# master_jorge.net
KiCad netlist of a schematic drawn in EAGLE
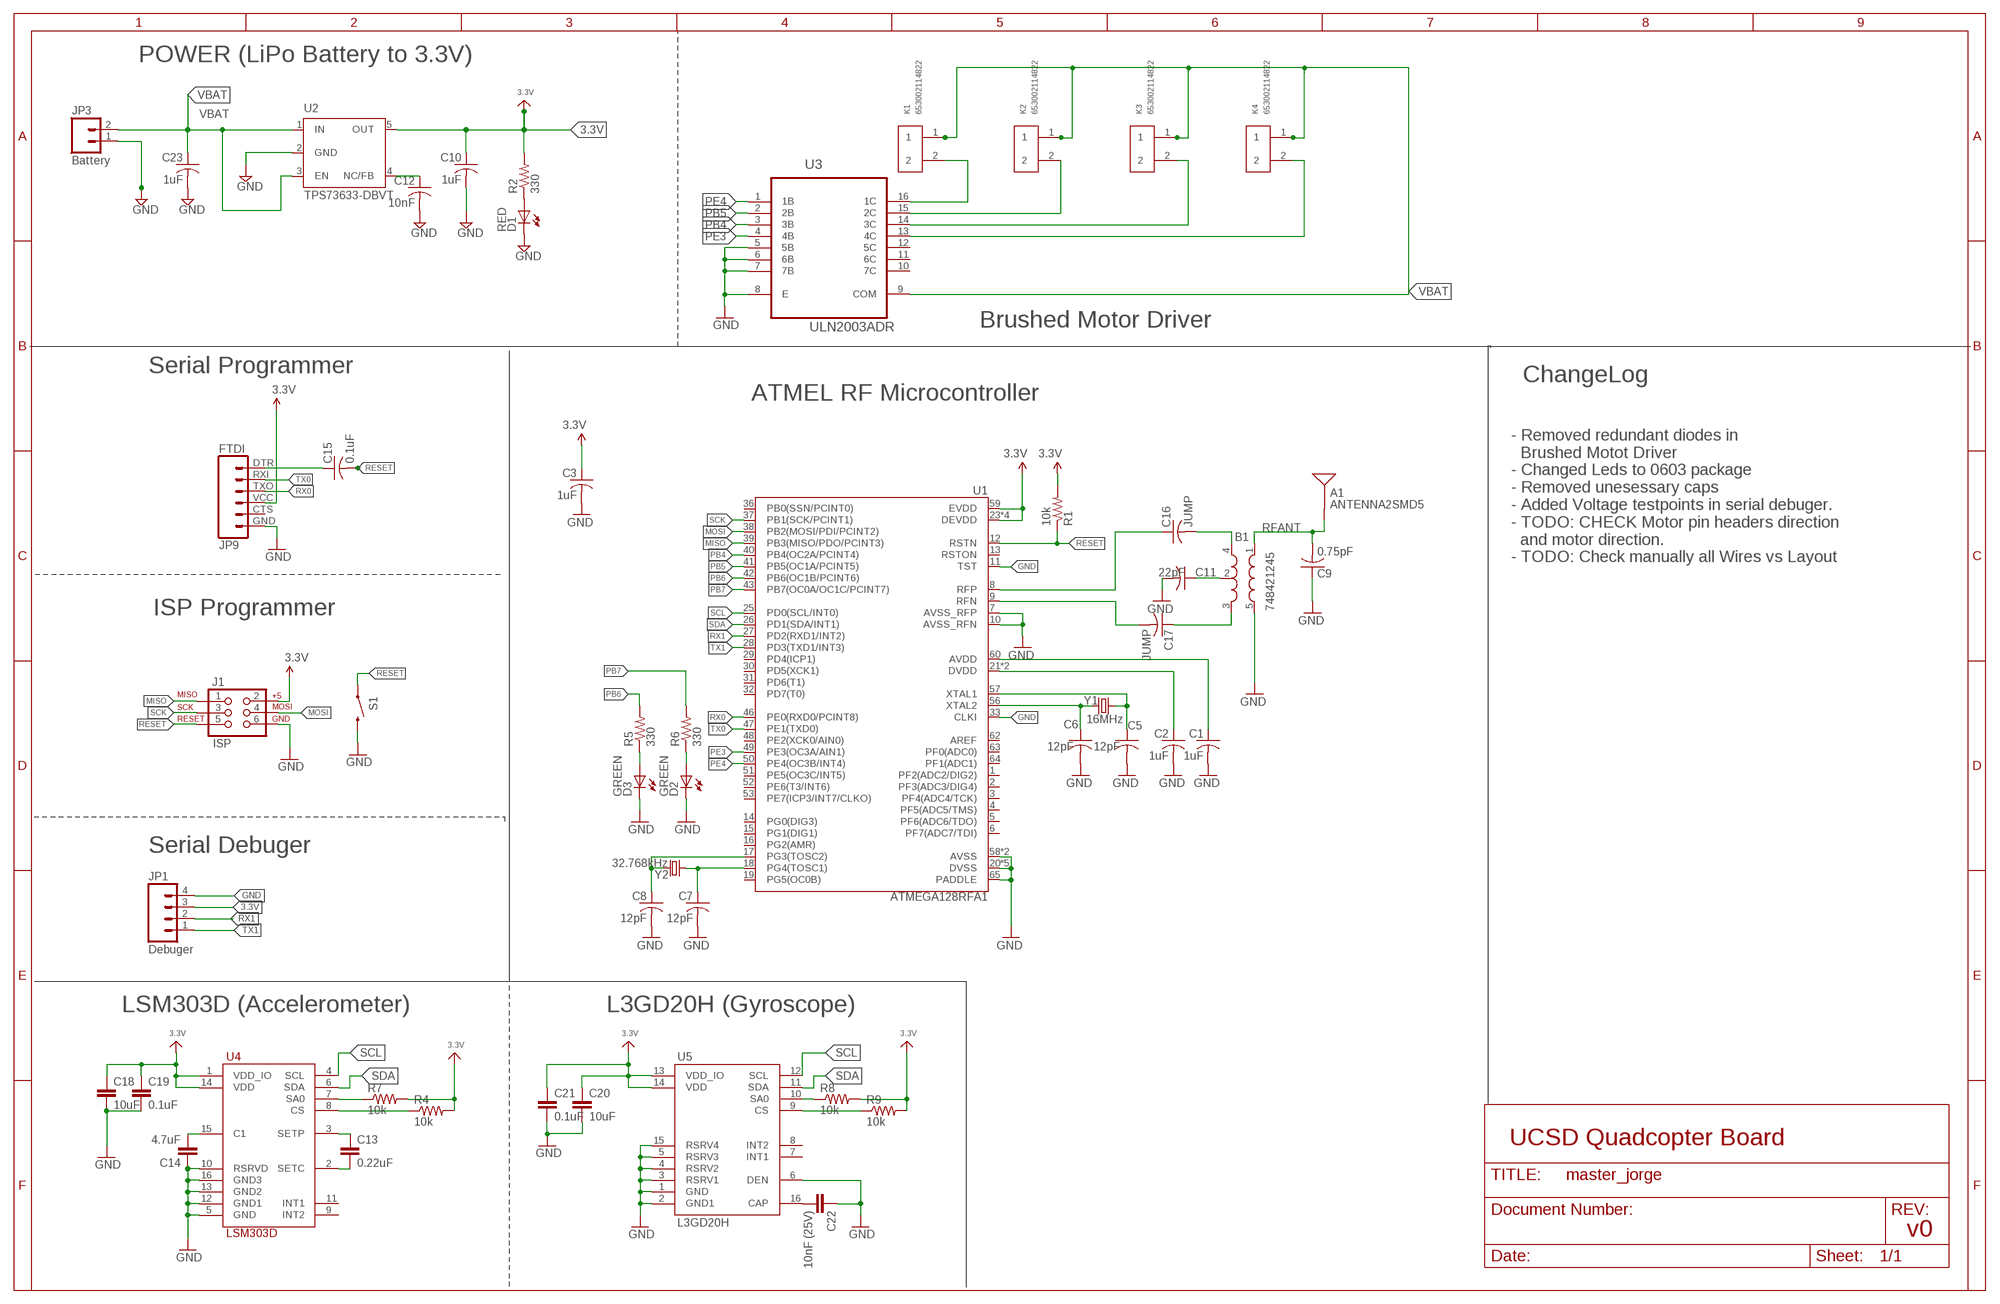
[diagram p0: schematic, sheet 1]

(export (version "E")
  (design (tool "Eeschema 10.0.6"))
  (components
    (comp (ref "A1")
      (value "ANTENNA2SMD5")
      (footprint "eagle-import:ANTENNA-CHIP5")
      (libsource (lib "eagle-import") (part "ANTENNA2SMD5"))
    )
    (comp (ref "B1")
      (value "748421245")
      (footprint "eagle-import:BALUN")
      (libsource (lib "eagle-import") (part "BALUN0805"))
    )
    (comp (ref "C1")
      (value "1uF")
      (footprint "eagle-import:C0805")
      (libsource (lib "eagle-import") (part "C-USC0805"))
    )
    (comp (ref "C2")
      (value "1uF")
      (footprint "eagle-import:C0805")
      (libsource (lib "eagle-import") (part "C-USC0805"))
    )
    (comp (ref "C3")
      (value "1uF")
      (footprint "eagle-import:C0805")
      (libsource (lib "eagle-import") (part "C-USC0805"))
    )
    (comp (ref "C5")
      (value "12pF")
      (footprint "eagle-import:C0805")
      (libsource (lib "eagle-import") (part "C-USC0805"))
    )
    (comp (ref "C6")
      (value "12pF")
      (footprint "eagle-import:C0805")
      (libsource (lib "eagle-import") (part "C-USC0805"))
    )
    (comp (ref "C7")
      (value "12pF")
      (footprint "eagle-import:C0805")
      (libsource (lib "eagle-import") (part "C-USC0805"))
    )
    (comp (ref "C8")
      (value "12pF")
      (footprint "eagle-import:C0805")
      (libsource (lib "eagle-import") (part "C-USC0805"))
    )
    (comp (ref "C9")
      (value "0.75pF")
      (footprint "eagle-import:C0805")
      (libsource (lib "eagle-import") (part "C-USC0805"))
    )
    (comp (ref "C10")
      (value "1uF")
      (footprint "eagle-import:C0805")
      (libsource (lib "eagle-import") (part "C-USC0805"))
    )
    (comp (ref "C11")
      (value "22pF")
      (footprint "eagle-import:C0805")
      (libsource (lib "eagle-import") (part "C-USC0805"))
    )
    (comp (ref "C12")
      (value "10nF")
      (footprint "eagle-import:C0805")
      (libsource (lib "eagle-import") (part "C-USC0805"))
    )
    (comp (ref "C13")
      (value "0.22uF")
      (footprint "eagle-import:0805")
      (libsource (lib "eagle-import") (part "CAP0805"))
    )
    (comp (ref "C14")
      (value "4.7uF")
      (footprint "eagle-import:0805")
      (libsource (lib "eagle-import") (part "CAP0805"))
    )
    (comp (ref "C15")
      (value "0.1uF")
      (footprint "eagle-import:C0805")
      (libsource (lib "eagle-import") (part "C-USC0805"))
    )
    (comp (ref "C16")
      (value "JUMP")
      (footprint "eagle-import:C0805")
      (libsource (lib "eagle-import") (part "C-USC0805"))
    )
    (comp (ref "C17")
      (value "JUMP")
      (footprint "eagle-import:C0805")
      (libsource (lib "eagle-import") (part "C-USC0805"))
    )
    (comp (ref "C18")
      (value "10uF")
      (footprint "eagle-import:0805")
      (libsource (lib "eagle-import") (part "CAP0805"))
    )
    (comp (ref "C19")
      (value "0.1uF")
      (footprint "eagle-import:0805")
      (libsource (lib "eagle-import") (part "CAP0805"))
    )
    (comp (ref "C20")
      (value "10uF")
      (footprint "eagle-import:0805")
      (libsource (lib "eagle-import") (part "CAP0805"))
    )
    (comp (ref "C21")
      (value "0.1uF")
      (footprint "eagle-import:0805")
      (libsource (lib "eagle-import") (part "CAP0805"))
    )
    (comp (ref "C22")
      (value "10nF (25V)")
      (footprint "eagle-import:0805")
      (libsource (lib "eagle-import") (part "CAP0805"))
    )
    (comp (ref "C23")
      (value "1uF")
      (footprint "eagle-import:C0805")
      (libsource (lib "eagle-import") (part "C-USC0805"))
    )
    (comp (ref "D1")
      (value "RED")
      (footprint "eagle-import:CHIPLED_0603")
      (libsource (lib "eagle-import") (part "LEDCHIPLED_0603"))
    )
    (comp (ref "D2")
      (value "GREEN")
      (footprint "eagle-import:CHIPLED_0603")
      (libsource (lib "eagle-import") (part "LEDCHIPLED_0603"))
    )
    (comp (ref "D3")
      (value "GREEN")
      (footprint "eagle-import:CHIPLED_0603")
      (libsource (lib "eagle-import") (part "LEDCHIPLED_0603"))
    )
    (comp (ref "J1")
      (value "ISP")
      (footprint "eagle-import:2X3-NS")
      (libsource (lib "eagle-import") (part "AVR_SPI_PRG_6NS"))
    )
    (comp (ref "JP1")
      (value "Debuger")
      (footprint "eagle-import:1X04")
      (libsource (lib "eagle-import") (part "M04PTH"))
    )
    (comp (ref "JP3")
      (value "Battery")
      (footprint "eagle-import:1X02")
      (libsource (lib "eagle-import") (part "M02PTH"))
    )
    (comp (ref "JP9")
      (value "FTDI")
      (footprint "eagle-import:FTDI_BASIC")
      (libsource (lib "eagle-import") (part "FTDI_BASICPTH"))
    )
    (comp (ref "K1")
      (value "653002114822")
      (footprint "eagle-import:653002114822")
      (libsource (lib "eagle-import") (part "653002114822"))
    )
    (comp (ref "K2")
      (value "653002114822")
      (footprint "eagle-import:653002114822")
      (libsource (lib "eagle-import") (part "653002114822"))
    )
    (comp (ref "K3")
      (value "653002114822")
      (footprint "eagle-import:653002114822")
      (libsource (lib "eagle-import") (part "653002114822"))
    )
    (comp (ref "K4")
      (value "653002114822")
      (footprint "eagle-import:653002114822")
      (libsource (lib "eagle-import") (part "653002114822"))
    )
    (comp (ref "R1")
      (value "10k")
      (footprint "eagle-import:R0805")
      (libsource (lib "eagle-import") (part "R-US_R0805"))
    )
    (comp (ref "R2")
      (value "330")
      (footprint "eagle-import:R0805")
      (libsource (lib "eagle-import") (part "R-US_R0805"))
    )
    (comp (ref "R4")
      (value "10k")
      (footprint "eagle-import:0805")
      (libsource (lib "eagle-import") (part "RESISTOR0805-RES"))
    )
    (comp (ref "R5")
      (value "330")
      (footprint "eagle-import:R0805")
      (libsource (lib "eagle-import") (part "R-US_R0805"))
    )
    (comp (ref "R6")
      (value "330")
      (footprint "eagle-import:R0805")
      (libsource (lib "eagle-import") (part "R-US_R0805"))
    )
    (comp (ref "R7")
      (value "10k")
      (footprint "eagle-import:0805")
      (libsource (lib "eagle-import") (part "RESISTOR0805-RES"))
    )
    (comp (ref "R8")
      (value "10k")
      (footprint "eagle-import:0805")
      (libsource (lib "eagle-import") (part "RESISTOR0805-RES"))
    )
    (comp (ref "R9")
      (value "10k")
      (footprint "eagle-import:0805")
      (libsource (lib "eagle-import") (part "RESISTOR0805-RES"))
    )
    (comp (ref "S1")
      (value "SWITCH-MOMENTARY-2SMD")
      (footprint "eagle-import:TACTILE_SWITCH_SMD")
      (libsource (lib "eagle-import") (part "SWITCH-MOMENTARY-2SMD"))
    )
    (comp (ref "U1")
      (value "ATMEGA128RFA1")
      (footprint "eagle-import:QFN-64")
      (libsource (lib "eagle-import") (part "ATMEGA128RFA1"))
    )
    (comp (ref "U2")
      (value "TPS73633-DBVT")
      (footprint "eagle-import:SOT23-DBV")
      (libsource (lib "eagle-import") (part "TPS73633-DBVT"))
    )
    (comp (ref "U3")
      (value "ULN2003ADR")
      (footprint "eagle-import:SOIC127P600X175-16N")
      (libsource (lib "eagle-import") (part "ULN2003ADR"))
    )
    (comp (ref "U4")
      (value "LSM303D")
      (footprint "eagle-import:LGA16_3X3MM")
      (libsource (lib "eagle-import") (part "LSM303D"))
    )
    (comp (ref "U5")
      (value "L3GD20H")
      (footprint "eagle-import:LGA16_3X3MM")
      (libsource (lib "eagle-import") (part "L3GD20H"))
    )
    (comp (ref "Y1")
      (value "16MHz")
      (footprint "eagle-import:CRYSTAL-SMD-5X3")
      (libsource (lib "eagle-import") (part "CRYSTAL5X3"))
    )
    (comp (ref "Y2")
      (value "32.768kHz")
      (footprint "eagle-import:CRYSTAL-32KHZ-SMD")
      (libsource (lib "eagle-import") (part "CRYSTAL32-SMD"))
    )
  )
  (nets
    (net (code "1") (name "/RFANT") (class "Default")
      (node (ref "A1") (pin "FEED") (pinfunction "SIGNAL_FEED") (pintype "bidirectional"))
      (node (ref "B1") (pin "1") (pinfunction "IN_1") (pintype "bidirectional"))
      (node (ref "C9") (pin "2") (pinfunction "2_2") (pintype "passive"))
    )
    (net (code "2") (name "3.3V") (class "Default")
      (node (ref "C10") (pin "1") (pinfunction "1_1") (pintype "passive"))
      (node (ref "C18") (pin "1") (pinfunction "1_1") (pintype "passive"))
      (node (ref "C19") (pin "1") (pinfunction "1_1") (pintype "passive"))
      (node (ref "C20") (pin "1") (pinfunction "1_1") (pintype "passive"))
      (node (ref "C21") (pin "1") (pinfunction "1_1") (pintype "passive"))
      (node (ref "C3") (pin "1") (pinfunction "1_1") (pintype "passive"))
      (node (ref "J1") (pin "2") (pinfunction "2_2") (pintype "passive"))
      (node (ref "JP1") (pin "3") (pinfunction "3_3") (pintype "passive"))
      (node (ref "JP9") (pin "VCC") (pinfunction "4_VCC") (pintype "passive"))
      (node (ref "R1") (pin "2") (pinfunction "2_2") (pintype "passive"))
      (node (ref "R2") (pin "2") (pinfunction "2_2") (pintype "passive"))
      (node (ref "R4") (pin "2") (pinfunction "2_2") (pintype "passive"))
      (node (ref "R7") (pin "2") (pinfunction "2_2") (pintype "passive"))
      (node (ref "R8") (pin "2") (pinfunction "2_2") (pintype "passive"))
      (node (ref "R9") (pin "2") (pinfunction "2_2") (pintype "passive"))
      (node (ref "U1") (pin "23") (pinfunction "DEVDD_23") (pintype "bidirectional"))
      (node (ref "U1") (pin "34") (pinfunction "DEVDD_34") (pintype "bidirectional"))
      (node (ref "U1") (pin "44") (pinfunction "DEVDD_44") (pintype "bidirectional"))
      (node (ref "U1") (pin "54") (pinfunction "DEVDD_54") (pintype "bidirectional"))
      (node (ref "U1") (pin "59") (pinfunction "EVDD_59") (pintype "bidirectional"))
      (node (ref "U2") (pin "5") (pinfunction "OUT_5") (pintype "passive"))
      (node (ref "U4") (pin "1") (pinfunction "VDD_IO_1") (pintype "bidirectional"))
      (node (ref "U4") (pin "14") (pinfunction "VDD_14") (pintype "bidirectional"))
      (node (ref "U5") (pin "13") (pinfunction "VDD_IO_13") (pintype "bidirectional"))
      (node (ref "U5") (pin "14") (pinfunction "VDD_14") (pintype "bidirectional"))
    )
    (net (code "3") (name "GND") (class "Default")
      (node (ref "B1") (pin "5") (pinfunction "GND_5") (pintype "bidirectional"))
      (node (ref "C1") (pin "2") (pinfunction "2_2") (pintype "passive"))
      (node (ref "C10") (pin "2") (pinfunction "2_2") (pintype "passive"))
      (node (ref "C11") (pin "2") (pinfunction "2_2") (pintype "passive"))
      (node (ref "C12") (pin "2") (pinfunction "2_2") (pintype "passive"))
      (node (ref "C14") (pin "1") (pinfunction "1_1") (pintype "passive"))
      (node (ref "C18") (pin "2") (pinfunction "2_2") (pintype "passive"))
      (node (ref "C19") (pin "2") (pinfunction "2_2") (pintype "passive"))
      (node (ref "C2") (pin "2") (pinfunction "2_2") (pintype "passive"))
      (node (ref "C20") (pin "2") (pinfunction "2_2") (pintype "passive"))
      (node (ref "C21") (pin "2") (pinfunction "2_2") (pintype "passive"))
      (node (ref "C22") (pin "1") (pinfunction "1_1") (pintype "passive"))
      (node (ref "C23") (pin "2") (pinfunction "2_2") (pintype "passive"))
      (node (ref "C3") (pin "2") (pinfunction "2_2") (pintype "passive"))
      (node (ref "C5") (pin "2") (pinfunction "2_2") (pintype "passive"))
      (node (ref "C6") (pin "2") (pinfunction "2_2") (pintype "passive"))
      (node (ref "C7") (pin "2") (pinfunction "2_2") (pintype "passive"))
      (node (ref "C8") (pin "2") (pinfunction "2_2") (pintype "passive"))
      (node (ref "C9") (pin "1") (pinfunction "1_1") (pintype "passive"))
      (node (ref "D1") (pin "C") (pinfunction "C_C") (pintype "passive"))
      (node (ref "D2") (pin "C") (pinfunction "C_C") (pintype "passive"))
      (node (ref "D3") (pin "C") (pinfunction "C_C") (pintype "passive"))
      (node (ref "J1") (pin "6") (pinfunction "6_6") (pintype "passive"))
      (node (ref "JP1") (pin "4") (pinfunction "4_4") (pintype "passive"))
      (node (ref "JP3") (pin "1") (pinfunction "1_1") (pintype "passive"))
      (node (ref "JP9") (pin "GND") (pinfunction "6_GND") (pintype "passive"))
      (node (ref "S1") (pin "3") (pinfunction "2_3") (pintype "passive"))
      (node (ref "U1") (pin "10") (pinfunction "AVSS_RFN_10") (pintype "bidirectional"))
      (node (ref "U1") (pin "11") (pinfunction "TST_11") (pintype "bidirectional"))
      (node (ref "U1") (pin "20") (pinfunction "DVSS_20") (pintype "bidirectional"))
      (node (ref "U1") (pin "24") (pinfunction "DVSS_24") (pintype "bidirectional"))
      (node (ref "U1") (pin "33") (pinfunction "CLKI_33") (pintype "bidirectional"))
      (node (ref "U1") (pin "35") (pinfunction "DVSS_35") (pintype "bidirectional"))
      (node (ref "U1") (pin "45") (pinfunction "DVSS_45") (pintype "bidirectional"))
      (node (ref "U1") (pin "55") (pinfunction "DVSS_55") (pintype "bidirectional"))
      (node (ref "U1") (pin "58") (pinfunction "AVSS_58") (pintype "bidirectional"))
      (node (ref "U1") (pin "61") (pinfunction "AVSS_61") (pintype "bidirectional"))
      (node (ref "U1") (pin "65") (pinfunction "PADDLE_65") (pintype "bidirectional"))
      (node (ref "U1") (pin "7") (pinfunction "AVSS_RFP_7") (pintype "bidirectional"))
      (node (ref "U2") (pin "2") (pinfunction "GND_2") (pintype "input"))
      (node (ref "U3") (pin "5") (pinfunction "5B_5") (pintype "input"))
      (node (ref "U3") (pin "6") (pinfunction "6B_6") (pintype "input"))
      (node (ref "U3") (pin "7") (pinfunction "7B_7") (pintype "input"))
      (node (ref "U3") (pin "8") (pinfunction "E_8") (pintype "input"))
      (node (ref "U4") (pin "10") (pinfunction "RSRVD_10") (pintype "bidirectional"))
      (node (ref "U4") (pin "12") (pinfunction "GND1_12") (pintype "bidirectional"))
      (node (ref "U4") (pin "13") (pinfunction "GND2_13") (pintype "bidirectional"))
      (node (ref "U4") (pin "16") (pinfunction "GND3_16") (pintype "bidirectional"))
      (node (ref "U4") (pin "5") (pinfunction "GND_5") (pintype "bidirectional"))
      (node (ref "U5") (pin "1") (pinfunction "GND_1") (pintype "bidirectional"))
      (node (ref "U5") (pin "15") (pinfunction "RSRV4_15") (pintype "bidirectional"))
      (node (ref "U5") (pin "2") (pinfunction "GND1_2") (pintype "bidirectional"))
      (node (ref "U5") (pin "3") (pinfunction "RSRV1_3") (pintype "bidirectional"))
      (node (ref "U5") (pin "4") (pinfunction "RSRV2_4") (pintype "bidirectional"))
      (node (ref "U5") (pin "5") (pinfunction "RSRV3_5") (pintype "bidirectional"))
      (node (ref "U5") (pin "6") (pinfunction "DEN_6") (pintype "bidirectional"))
    )
    (net (code "4") (name "MISO") (class "Default")
      (node (ref "J1") (pin "1") (pinfunction "1_1") (pintype "passive"))
      (node (ref "U1") (pin "39") (pinfunction "PB3(MISO/PDO/PCINT3)_39") (pintype "bidirectional"))
    )
    (net (code "5") (name "MOSI") (class "Default")
      (node (ref "J1") (pin "4") (pinfunction "4_4") (pintype "passive"))
      (node (ref "U1") (pin "38") (pinfunction "PB2(MOSI/PDI/PCINT2)_38") (pintype "bidirectional"))
    )
    (net (code "6") (name "Net-(B1-GND-Pad2)") (class "Default")
      (node (ref "B1") (pin "2") (pinfunction "GND_2") (pintype "bidirectional"))
      (node (ref "C11") (pin "1") (pinfunction "1_1") (pintype "passive"))
    )
    (net (code "7") (name "Net-(B1-OUT1)") (class "Default")
      (node (ref "B1") (pin "4") (pinfunction "OUT1_4") (pintype "bidirectional"))
      (node (ref "C16") (pin "2") (pinfunction "2_2") (pintype "passive"))
    )
    (net (code "8") (name "Net-(B1-OUT2)") (class "Default")
      (node (ref "B1") (pin "3") (pinfunction "OUT2_3") (pintype "bidirectional"))
      (node (ref "C17") (pin "1") (pinfunction "1_1") (pintype "passive"))
    )
    (net (code "9") (name "Net-(C2-Pad1)") (class "Default")
      (node (ref "C2") (pin "1") (pinfunction "1_1") (pintype "passive"))
      (node (ref "U1") (pin "21") (pinfunction "DVDD_21") (pintype "bidirectional"))
      (node (ref "U1") (pin "22") (pinfunction "DVDD_22") (pintype "bidirectional"))
    )
    (net (code "10") (name "Net-(D1-PadA)") (class "Default")
      (node (ref "D1") (pin "A") (pinfunction "A_A") (pintype "passive"))
      (node (ref "R2") (pin "1") (pinfunction "1_1") (pintype "passive"))
    )
    (net (code "11") (name "Net-(D2-PadA)") (class "Default")
      (node (ref "D2") (pin "A") (pinfunction "A_A") (pintype "passive"))
      (node (ref "R6") (pin "1") (pinfunction "1_1") (pintype "passive"))
    )
    (net (code "12") (name "Net-(D3-PadA)") (class "Default")
      (node (ref "D3") (pin "A") (pinfunction "A_A") (pintype "passive"))
      (node (ref "R5") (pin "1") (pinfunction "1_1") (pintype "passive"))
    )
    (net (code "13") (name "Net-(JP9-1)") (class "Default")
      (node (ref "C15") (pin "1") (pinfunction "1_1") (pintype "passive"))
      (node (ref "JP9") (pin "DTR") (pinfunction "1_DTR") (pintype "passive"))
    )
    (net (code "14") (name "Net-(U1-AVDD)") (class "Default")
      (node (ref "C1") (pin "1") (pinfunction "1_1") (pintype "passive"))
      (node (ref "U1") (pin "60") (pinfunction "AVDD_60") (pintype "bidirectional"))
    )
    (net (code "15") (name "Net-(U1-PG3(TOSC2))") (class "Default")
      (node (ref "C8") (pin "1") (pinfunction "1_1") (pintype "passive"))
      (node (ref "U1") (pin "17") (pinfunction "PG3(TOSC2)_17") (pintype "bidirectional"))
      (node (ref "Y2") (pin "X2") (pinfunction "2_X2") (pintype "passive"))
    )
    (net (code "16") (name "Net-(U1-PG4(TOSC1))") (class "Default")
      (node (ref "C7") (pin "1") (pinfunction "1_1") (pintype "passive"))
      (node (ref "U1") (pin "18") (pinfunction "PG4(TOSC1)_18") (pintype "bidirectional"))
      (node (ref "Y2") (pin "X1") (pinfunction "1_X1") (pintype "passive"))
    )
    (net (code "17") (name "Net-(U1-RFN)") (class "Default")
      (node (ref "C17") (pin "2") (pinfunction "2_2") (pintype "passive"))
      (node (ref "U1") (pin "9") (pinfunction "RFN_9") (pintype "bidirectional"))
    )
    (net (code "18") (name "Net-(U1-RFP)") (class "Default")
      (node (ref "C16") (pin "1") (pinfunction "1_1") (pintype "passive"))
      (node (ref "U1") (pin "8") (pinfunction "RFP_8") (pintype "bidirectional"))
    )
    (net (code "19") (name "Net-(U1-XTAL1)") (class "Default")
      (node (ref "C5") (pin "1") (pinfunction "1_1") (pintype "passive"))
      (node (ref "U1") (pin "57") (pinfunction "XTAL1_57") (pintype "bidirectional"))
      (node (ref "Y1") (pin "3") (pinfunction "2_3") (pintype "passive"))
    )
    (net (code "20") (name "Net-(U1-XTAL2)") (class "Default")
      (node (ref "C6") (pin "1") (pinfunction "1_1") (pintype "passive"))
      (node (ref "U1") (pin "56") (pinfunction "XTAL2_56") (pintype "bidirectional"))
      (node (ref "Y1") (pin "1") (pinfunction "1_1") (pintype "passive"))
    )
    (net (code "21") (name "Net-(U2-NC{slash}FB)") (class "Default")
      (node (ref "C12") (pin "1") (pinfunction "1_1") (pintype "passive"))
      (node (ref "U2") (pin "4") (pinfunction "NC/FB_4") (pintype "passive"))
    )
    (net (code "22") (name "Net-(U3-1C)") (class "Default")
      (node (ref "K1") (pin "2") (pinfunction "2_2") (pintype "bidirectional"))
      (node (ref "U3") (pin "16") (pinfunction "1C_16") (pintype "output"))
    )
    (net (code "23") (name "Net-(U3-2C)") (class "Default")
      (node (ref "K2") (pin "2") (pinfunction "2_2") (pintype "bidirectional"))
      (node (ref "U3") (pin "15") (pinfunction "2C_15") (pintype "output"))
    )
    (net (code "24") (name "Net-(U3-3C)") (class "Default")
      (node (ref "K3") (pin "2") (pinfunction "2_2") (pintype "bidirectional"))
      (node (ref "U3") (pin "14") (pinfunction "3C_14") (pintype "output"))
    )
    (net (code "25") (name "Net-(U3-4C)") (class "Default")
      (node (ref "K4") (pin "2") (pinfunction "2_2") (pintype "bidirectional"))
      (node (ref "U3") (pin "13") (pinfunction "4C_13") (pintype "output"))
    )
    (net (code "26") (name "Net-(U4-C1)") (class "Default")
      (node (ref "C14") (pin "2") (pinfunction "2_2") (pintype "passive"))
      (node (ref "U4") (pin "15") (pinfunction "C1_15") (pintype "bidirectional"))
    )
    (net (code "27") (name "Net-(U4-CS)") (class "Default")
      (node (ref "R4") (pin "1") (pinfunction "1_1") (pintype "passive"))
      (node (ref "U4") (pin "8") (pinfunction "CS_8") (pintype "bidirectional"))
    )
    (net (code "28") (name "Net-(U4-SA0)") (class "Default")
      (node (ref "R7") (pin "1") (pinfunction "1_1") (pintype "passive"))
      (node (ref "U4") (pin "7") (pinfunction "SA0_7") (pintype "bidirectional"))
    )
    (net (code "29") (name "Net-(U4-SETC)") (class "Default")
      (node (ref "C13") (pin "2") (pinfunction "2_2") (pintype "passive"))
      (node (ref "U4") (pin "2") (pinfunction "SETC_2") (pintype "bidirectional"))
    )
    (net (code "30") (name "Net-(U4-SETP)") (class "Default")
      (node (ref "C13") (pin "1") (pinfunction "1_1") (pintype "passive"))
      (node (ref "U4") (pin "3") (pinfunction "SETP_3") (pintype "bidirectional"))
    )
    (net (code "31") (name "Net-(U5-CAP)") (class "Default")
      (node (ref "C22") (pin "2") (pinfunction "2_2") (pintype "passive"))
      (node (ref "U5") (pin "16") (pinfunction "CAP_16") (pintype "bidirectional"))
    )
    (net (code "32") (name "Net-(U5-CS)") (class "Default")
      (node (ref "R9") (pin "1") (pinfunction "1_1") (pintype "passive"))
      (node (ref "U5") (pin "9") (pinfunction "CS_9") (pintype "bidirectional"))
    )
    (net (code "33") (name "Net-(U5-SA0)") (class "Default")
      (node (ref "R8") (pin "1") (pinfunction "1_1") (pintype "passive"))
      (node (ref "U5") (pin "10") (pinfunction "SA0_10") (pintype "bidirectional"))
    )
    (net (code "34") (name "PB4") (class "Default")
      (node (ref "U1") (pin "40") (pinfunction "PB4(OC2A/PCINT4)_40") (pintype "bidirectional"))
      (node (ref "U3") (pin "3") (pinfunction "3B_3") (pintype "input"))
    )
    (net (code "35") (name "PB5") (class "Default")
      (node (ref "U1") (pin "41") (pinfunction "PB5(OC1A/PCINT5)_41") (pintype "bidirectional"))
      (node (ref "U3") (pin "2") (pinfunction "2B_2") (pintype "input"))
    )
    (net (code "36") (name "PB6") (class "Default")
      (node (ref "R5") (pin "2") (pinfunction "2_2") (pintype "passive"))
      (node (ref "U1") (pin "42") (pinfunction "PB6(OC1B/PCINT6)_42") (pintype "bidirectional"))
    )
    (net (code "37") (name "PB7") (class "Default")
      (node (ref "R6") (pin "2") (pinfunction "2_2") (pintype "passive"))
      (node (ref "U1") (pin "43") (pinfunction "PB7(OC0A/OC1C/PCINT7)_43") (pintype "bidirectional"))
    )
    (net (code "38") (name "PE3") (class "Default")
      (node (ref "U1") (pin "49") (pinfunction "PE3(OC3A/AIN1)_49") (pintype "bidirectional"))
      (node (ref "U3") (pin "4") (pinfunction "4B_4") (pintype "input"))
    )
    (net (code "39") (name "PE4") (class "Default")
      (node (ref "U1") (pin "50") (pinfunction "PE4(OC3B/INT4)_50") (pintype "bidirectional"))
      (node (ref "U3") (pin "1") (pinfunction "1B_1") (pintype "input"))
    )
    (net (code "40") (name "RESET") (class "Default")
      (node (ref "C15") (pin "2") (pinfunction "2_2") (pintype "passive"))
      (node (ref "J1") (pin "5") (pinfunction "5_5") (pintype "passive"))
      (node (ref "R1") (pin "1") (pinfunction "1_1") (pintype "passive"))
      (node (ref "S1") (pin "1") (pinfunction "1_1") (pintype "passive"))
      (node (ref "U1") (pin "12") (pinfunction "RSTN_12") (pintype "bidirectional"))
    )
    (net (code "41") (name "RX0") (class "Default")
      (node (ref "JP9") (pin "TXO") (pinfunction "3_TXO") (pintype "passive"))
      (node (ref "U1") (pin "46") (pinfunction "PE0(RXD0/PCINT8)_46") (pintype "bidirectional"))
    )
    (net (code "42") (name "RX1") (class "Default")
      (node (ref "JP1") (pin "2") (pinfunction "2_2") (pintype "passive"))
      (node (ref "U1") (pin "27") (pinfunction "PD2(RXD1/INT2)_27") (pintype "bidirectional"))
    )
    (net (code "43") (name "SCK") (class "Default")
      (node (ref "J1") (pin "3") (pinfunction "3_3") (pintype "passive"))
      (node (ref "U1") (pin "37") (pinfunction "PB1(SCK/PCINT1)_37") (pintype "bidirectional"))
    )
    (net (code "44") (name "SCL") (class "Default")
      (node (ref "U1") (pin "25") (pinfunction "PD0(SCL/INT0)_25") (pintype "bidirectional"))
      (node (ref "U4") (pin "4") (pinfunction "SCL_4") (pintype "bidirectional"))
      (node (ref "U5") (pin "12") (pinfunction "SCL_12") (pintype "bidirectional"))
    )
    (net (code "45") (name "SDA") (class "Default")
      (node (ref "U1") (pin "26") (pinfunction "PD1(SDA/INT1)_26") (pintype "bidirectional"))
      (node (ref "U4") (pin "6") (pinfunction "SDA_6") (pintype "bidirectional"))
      (node (ref "U5") (pin "11") (pinfunction "SDA_11") (pintype "bidirectional"))
    )
    (net (code "46") (name "TX0") (class "Default")
      (node (ref "JP9") (pin "RXI") (pinfunction "2_RXI") (pintype "passive"))
      (node (ref "U1") (pin "47") (pinfunction "PE1(TXD0)_47") (pintype "bidirectional"))
    )
    (net (code "47") (name "TX1") (class "Default")
      (node (ref "JP1") (pin "1") (pinfunction "1_1") (pintype "passive"))
      (node (ref "U1") (pin "28") (pinfunction "PD3(TXD1/INT3)_28") (pintype "bidirectional"))
    )
    (net (code "48") (name "VBAT") (class "Default")
      (node (ref "C23") (pin "1") (pinfunction "1_1") (pintype "passive"))
      (node (ref "JP3") (pin "2") (pinfunction "2_2") (pintype "passive"))
      (node (ref "K1") (pin "1") (pinfunction "1_1") (pintype "bidirectional"))
      (node (ref "K2") (pin "1") (pinfunction "1_1") (pintype "bidirectional"))
      (node (ref "K3") (pin "1") (pinfunction "1_1") (pintype "bidirectional"))
      (node (ref "K4") (pin "1") (pinfunction "1_1") (pintype "bidirectional"))
      (node (ref "U2") (pin "1") (pinfunction "IN_1") (pintype "input"))
      (node (ref "U2") (pin "3") (pinfunction "EN_3") (pintype "power_in"))
      (node (ref "U3") (pin "9") (pinfunction "COM_9") (pintype "output"))
    )
    (net (code "49") (name "unconnected-(JP9-5-PadCTS)") (class "Default")
      (node (ref "JP9") (pin "CTS") (pinfunction "5_CTS") (pintype "passive"))
    )
    (net (code "50") (name "unconnected-(U1-AREF-Pad62)") (class "Default")
      (node (ref "U1") (pin "62") (pinfunction "AREF_62") (pintype "bidirectional"))
    )
    (net (code "51") (name "unconnected-(U1-PB0(SSN{slash}PCINT0)-Pad36)") (class "Default")
      (node (ref "U1") (pin "36") (pinfunction "PB0(SSN/PCINT0)_36") (pintype "bidirectional"))
    )
    (net (code "52") (name "unconnected-(U1-PD4(ICP1)-Pad29)") (class "Default")
      (node (ref "U1") (pin "29") (pinfunction "PD4(ICP1)_29") (pintype "bidirectional"))
    )
    (net (code "53") (name "unconnected-(U1-PD5(XCK1)-Pad30)") (class "Default")
      (node (ref "U1") (pin "30") (pinfunction "PD5(XCK1)_30") (pintype "bidirectional"))
    )
    (net (code "54") (name "unconnected-(U1-PD6(T1)-Pad31)") (class "Default")
      (node (ref "U1") (pin "31") (pinfunction "PD6(T1)_31") (pintype "bidirectional"))
    )
    (net (code "55") (name "unconnected-(U1-PD7(T0)-Pad32)") (class "Default")
      (node (ref "U1") (pin "32") (pinfunction "PD7(T0)_32") (pintype "bidirectional"))
    )
    (net (code "56") (name "unconnected-(U1-PE2(XCK0{slash}AIN0)-Pad48)") (class "Default")
      (node (ref "U1") (pin "48") (pinfunction "PE2(XCK0/AIN0)_48") (pintype "bidirectional"))
    )
    (net (code "57") (name "unconnected-(U1-PE5(OC3C{slash}INT5)-Pad51)") (class "Default")
      (node (ref "U1") (pin "51") (pinfunction "PE5(OC3C/INT5)_51") (pintype "bidirectional"))
    )
    (net (code "58") (name "unconnected-(U1-PE6(T3{slash}INT6)-Pad52)") (class "Default")
      (node (ref "U1") (pin "52") (pinfunction "PE6(T3/INT6)_52") (pintype "bidirectional"))
    )
    (net (code "59") (name "unconnected-(U1-PE7(ICP3{slash}INT7{slash}CLKO)-Pad53)") (class "Default")
      (node (ref "U1") (pin "53") (pinfunction "PE7(ICP3/INT7/CLKO)_53") (pintype "bidirectional"))
    )
    (net (code "60") (name "unconnected-(U1-PF0(ADC0)-Pad63)") (class "Default")
      (node (ref "U1") (pin "63") (pinfunction "PF0(ADC0)_63") (pintype "bidirectional"))
    )
    (net (code "61") (name "unconnected-(U1-PF1(ADC1)-Pad64)") (class "Default")
      (node (ref "U1") (pin "64") (pinfunction "PF1(ADC1)_64") (pintype "bidirectional"))
    )
    (net (code "62") (name "unconnected-(U1-PF2(ADC2{slash}DIG2)-Pad1)") (class "Default")
      (node (ref "U1") (pin "1") (pinfunction "PF2(ADC2/DIG2)_1") (pintype "bidirectional"))
    )
    (net (code "63") (name "unconnected-(U1-PF3(ADC3{slash}DIG4)-Pad2)") (class "Default")
      (node (ref "U1") (pin "2") (pinfunction "PF3(ADC3/DIG4)_2") (pintype "bidirectional"))
    )
    (net (code "64") (name "unconnected-(U1-PF4(ADC4{slash}TCK)-Pad3)") (class "Default")
      (node (ref "U1") (pin "3") (pinfunction "PF4(ADC4/TCK)_3") (pintype "bidirectional"))
    )
    (net (code "65") (name "unconnected-(U1-PF5(ADC5{slash}TMS)-Pad4)") (class "Default")
      (node (ref "U1") (pin "4") (pinfunction "PF5(ADC5/TMS)_4") (pintype "bidirectional"))
    )
    (net (code "66") (name "unconnected-(U1-PF6(ADC6{slash}TDO)-Pad5)") (class "Default")
      (node (ref "U1") (pin "5") (pinfunction "PF6(ADC6/TDO)_5") (pintype "bidirectional"))
    )
    (net (code "67") (name "unconnected-(U1-PF7(ADC7{slash}TDI)-Pad6)") (class "Default")
      (node (ref "U1") (pin "6") (pinfunction "PF7(ADC7/TDI)_6") (pintype "bidirectional"))
    )
    (net (code "68") (name "unconnected-(U1-PG0(DIG3)-Pad14)") (class "Default")
      (node (ref "U1") (pin "14") (pinfunction "PG0(DIG3)_14") (pintype "bidirectional"))
    )
    (net (code "69") (name "unconnected-(U1-PG1(DIG1)-Pad15)") (class "Default")
      (node (ref "U1") (pin "15") (pinfunction "PG1(DIG1)_15") (pintype "bidirectional"))
    )
    (net (code "70") (name "unconnected-(U1-PG2(AMR)-Pad16)") (class "Default")
      (node (ref "U1") (pin "16") (pinfunction "PG2(AMR)_16") (pintype "bidirectional"))
    )
    (net (code "71") (name "unconnected-(U1-PG5(OC0B)-Pad19)") (class "Default")
      (node (ref "U1") (pin "19") (pinfunction "PG5(OC0B)_19") (pintype "bidirectional"))
    )
    (net (code "72") (name "unconnected-(U1-RSTON-Pad13)") (class "Default")
      (node (ref "U1") (pin "13") (pinfunction "RSTON_13") (pintype "bidirectional"))
    )
    (net (code "73") (name "unconnected-(U3-5C-Pad12)") (class "Default")
      (node (ref "U3") (pin "12") (pinfunction "5C_12") (pintype "output"))
    )
    (net (code "74") (name "unconnected-(U3-6C-Pad11)") (class "Default")
      (node (ref "U3") (pin "11") (pinfunction "6C_11") (pintype "output"))
    )
    (net (code "75") (name "unconnected-(U3-7C-Pad10)") (class "Default")
      (node (ref "U3") (pin "10") (pinfunction "7C_10") (pintype "output"))
    )
    (net (code "76") (name "unconnected-(U4-INT1-Pad11)") (class "Default")
      (node (ref "U4") (pin "11") (pinfunction "INT1_11") (pintype "bidirectional"))
    )
    (net (code "77") (name "unconnected-(U4-INT2-Pad9)") (class "Default")
      (node (ref "U4") (pin "9") (pinfunction "INT2_9") (pintype "bidirectional"))
    )
    (net (code "78") (name "unconnected-(U5-INT1-Pad7)") (class "Default")
      (node (ref "U5") (pin "7") (pinfunction "INT1_7") (pintype "bidirectional"))
    )
    (net (code "79") (name "unconnected-(U5-INT2-Pad8)") (class "Default")
      (node (ref "U5") (pin "8") (pinfunction "INT2_8") (pintype "bidirectional"))
    )
  )
)
